# SBH_BMS.net
KiCad netlist of a schematic drawn in Altium Designer
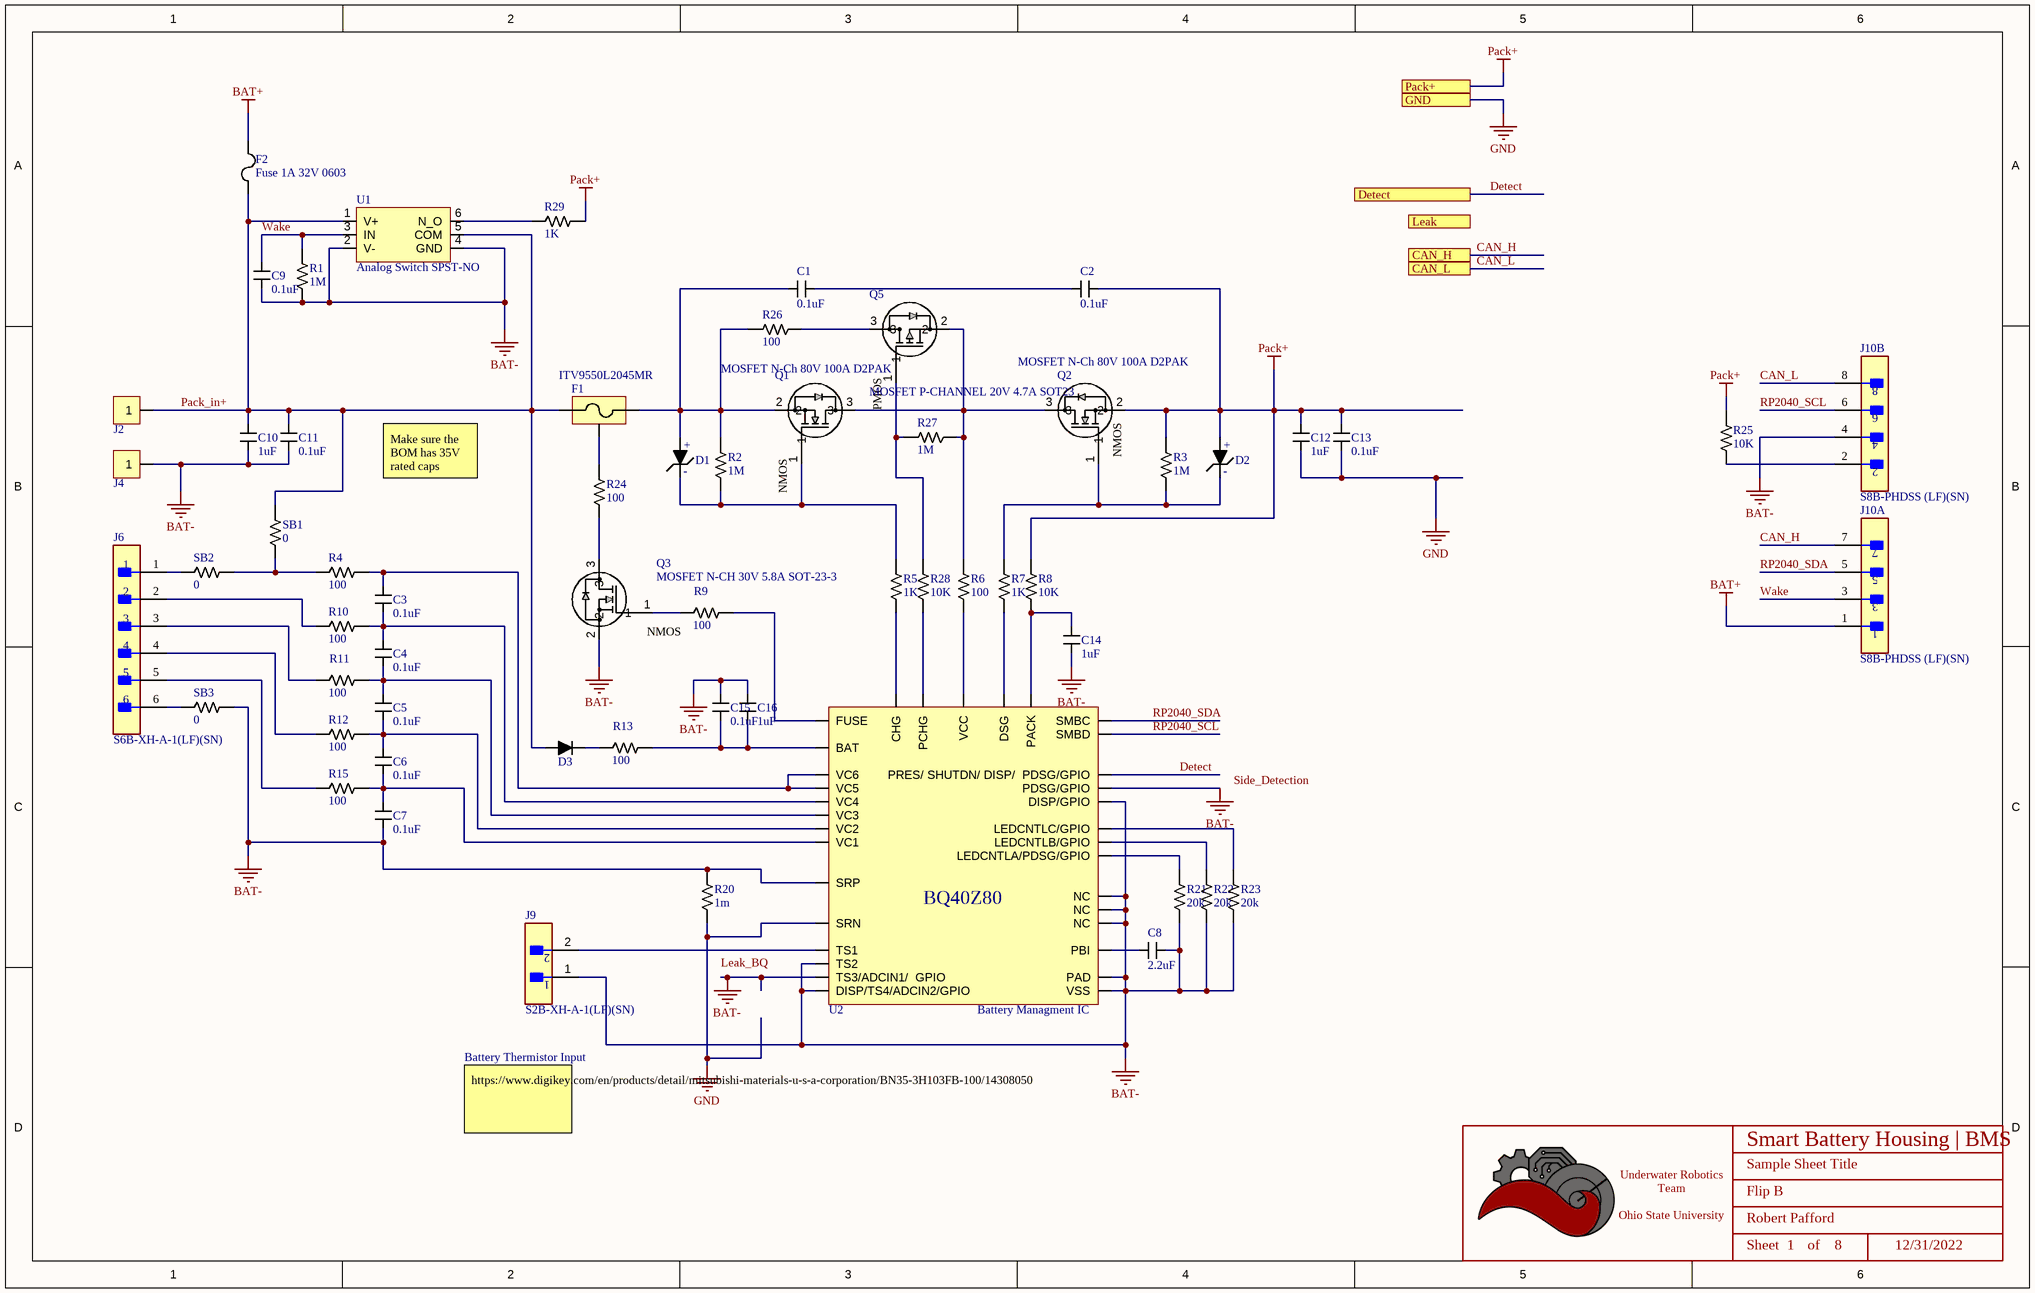
[diagram p0: SBH_BMS.SchDoc]

(export (version "E")
  (design (tool "Eeschema 10.0.6"))
  (components
    (comp (ref "C1")
      (value "0.1uF")
      (footprint "CAPACITOR_0402")
      (description "Cap 100nF 25V +/-10%\r\nCeramic 0402")
      (fields
        (field (name "TOLERANCE") "+/- 10%")
        (field (name "VOLTAGE") "25V")
        (field (name "MADE BY") "Robert Pafford")
      )
      (libsource (lib "Capacitors") (part "CAPACITOR_0.1uF_0402"))
    )
    (comp (ref "C2")
      (value "0.1uF")
      (footprint "CAPACITOR_0402")
      (description "Cap 100nF 25V +/-10%\r\nCeramic 0402")
      (fields
        (field (name "TOLERANCE") "+/- 10%")
        (field (name "VOLTAGE") "25V")
        (field (name "MADE BY") "Robert Pafford")
      )
      (libsource (lib "Capacitors") (part "CAPACITOR_0.1uF_0402"))
    )
    (comp (ref "C3")
      (value "0.1uF")
      (footprint "CAPACITOR_0402")
      (description "Cap 100nF 25V +/-10%\r\nCeramic 0402")
      (fields
        (field (name "TOLERANCE") "+/- 10%")
        (field (name "VOLTAGE") "25V")
        (field (name "MADE BY") "Robert Pafford")
      )
      (libsource (lib "Capacitors") (part "CAPACITOR_0.1uF_0402"))
    )
    (comp (ref "C4")
      (value "0.1uF")
      (footprint "CAPACITOR_0402")
      (description "Cap 100nF 25V +/-10%\r\nCeramic 0402")
      (fields
        (field (name "TOLERANCE") "+/- 10%")
        (field (name "VOLTAGE") "25V")
        (field (name "MADE BY") "Robert Pafford")
      )
      (libsource (lib "Capacitors") (part "CAPACITOR_0.1uF_0402"))
    )
    (comp (ref "C5")
      (value "0.1uF")
      (footprint "CAPACITOR_0402")
      (description "Cap 100nF 25V +/-10%\r\nCeramic 0402")
      (fields
        (field (name "TOLERANCE") "+/- 10%")
        (field (name "VOLTAGE") "25V")
        (field (name "MADE BY") "Robert Pafford")
      )
      (libsource (lib "Capacitors") (part "CAPACITOR_0.1uF_0402"))
    )
    (comp (ref "C6")
      (value "0.1uF")
      (footprint "CAPACITOR_0402")
      (description "Cap 100nF 25V +/-10%\r\nCeramic 0402")
      (fields
        (field (name "TOLERANCE") "+/- 10%")
        (field (name "VOLTAGE") "25V")
        (field (name "MADE BY") "Robert Pafford")
      )
      (libsource (lib "Capacitors") (part "CAPACITOR_0.1uF_0402"))
    )
    (comp (ref "C7")
      (value "0.1uF")
      (footprint "CAPACITOR_0402")
      (description "Cap 100nF 25V +/-10%\r\nCeramic 0402")
      (fields
        (field (name "TOLERANCE") "+/- 10%")
        (field (name "VOLTAGE") "25V")
        (field (name "MADE BY") "Robert Pafford")
      )
      (libsource (lib "Capacitors") (part "CAPACITOR_0.1uF_0402"))
    )
    (comp (ref "C8")
      (value "2.2uF")
      (footprint "CAPACITOR_0402")
      (description "Cap 2.2uF 35V +/-10%\r\nCeramic 0402")
      (fields
        (field (name "TOLERANCE") "+/- 10%")
        (field (name "VOLTAGE") "35V")
        (field (name "MADE BY") "Flip B")
      )
      (libsource (lib "Capacitors") (part "CAPACITOR_2.2uF_0402"))
    )
    (comp (ref "C9")
      (value "0.1uF")
      (footprint "CAPACITOR_0402")
      (description "Cap 100nF 25V +/-10%\r\nCeramic 0402")
      (fields
        (field (name "TOLERANCE") "+/- 10%")
        (field (name "VOLTAGE") "25V")
        (field (name "MADE BY") "Robert Pafford")
      )
      (libsource (lib "Capacitors") (part "CAPACITOR_0.1uF_0402"))
    )
    (comp (ref "C10")
      (value "1uF")
      (footprint "CAPACITOR_0402")
      (description "Cap 1uF 16V +/-10%\r\nCeramic 0402")
      (fields
        (field (name "TOLERANCE") "+/- 10%")
        (field (name "VOLTAGE") "16V")
        (field (name "MADE BY") "Robert Pafford")
      )
      (libsource (lib "Capacitors") (part "CAPACITOR_1uF_0402"))
    )
    (comp (ref "C11")
      (value "0.1uF")
      (footprint "CAPACITOR_0402")
      (description "Cap 100nF 25V +/-10%\r\nCeramic 0402")
      (fields
        (field (name "TOLERANCE") "+/- 10%")
        (field (name "VOLTAGE") "25V")
        (field (name "MADE BY") "Robert Pafford")
      )
      (libsource (lib "Capacitors") (part "CAPACITOR_0.1uF_0402"))
    )
    (comp (ref "C12")
      (value "1uF")
      (footprint "CAPACITOR_0402")
      (description "Cap 1uF 16V +/-10%\r\nCeramic 0402")
      (fields
        (field (name "TOLERANCE") "+/- 10%")
        (field (name "VOLTAGE") "16V")
        (field (name "MADE BY") "Robert Pafford")
      )
      (libsource (lib "Capacitors") (part "CAPACITOR_1uF_0402"))
    )
    (comp (ref "C13")
      (value "0.1uF")
      (footprint "CAPACITOR_0402")
      (description "Cap 100nF 25V +/-10%\r\nCeramic 0402")
      (fields
        (field (name "TOLERANCE") "+/- 10%")
        (field (name "VOLTAGE") "25V")
        (field (name "MADE BY") "Robert Pafford")
      )
      (libsource (lib "Capacitors") (part "CAPACITOR_0.1uF_0402"))
    )
    (comp (ref "C14")
      (value "1uF")
      (footprint "CAPACITOR_0402")
      (description "Cap 1uF 16V +/-10%\r\nCeramic 0402")
      (fields
        (field (name "TOLERANCE") "+/- 10%")
        (field (name "VOLTAGE") "16V")
        (field (name "MADE BY") "Robert Pafford")
      )
      (libsource (lib "Capacitors") (part "CAPACITOR_1uF_0402"))
    )
    (comp (ref "C15")
      (value "0.1uF")
      (footprint "CAPACITOR_0402")
      (description "Cap 100nF 25V +/-10%\r\nCeramic 0402")
      (fields
        (field (name "TOLERANCE") "+/- 10%")
        (field (name "VOLTAGE") "25V")
        (field (name "MADE BY") "Robert Pafford")
      )
      (libsource (lib "Capacitors") (part "CAPACITOR_0.1uF_0402"))
    )
    (comp (ref "C16")
      (value "1uF")
      (footprint "CAPACITOR_0402")
      (description "Cap 1uF 16V +/-10%\r\nCeramic 0402")
      (fields
        (field (name "TOLERANCE") "+/- 10%")
        (field (name "VOLTAGE") "16V")
        (field (name "MADE BY") "Robert Pafford")
      )
      (libsource (lib "Capacitors") (part "CAPACITOR_1uF_0402"))
    )
    (comp (ref "D1")
      (value "Zener_Diode_16V_500mW")
      (footprint "SOD-123")
      (description "Zener Diode ¦ 16 V ¦ 500 mW ¦ SOD-123")
      (fields (field (name "POWER") "500mW") (field (name "MADE BY") "Flip B"))
      (libsource (lib "Diodes") (part "Zener_Diode_16V_500mW"))
    )
    (comp (ref "D2")
      (value "Zener_Diode_16V_500mW")
      (footprint "SOD-123")
      (description "Zener Diode ¦ 16 V ¦ 500 mW ¦ SOD-123")
      (fields (field (name "POWER") "500mW") (field (name "MADE BY") "Flip B"))
      (libsource (lib "Diodes") (part "Zener_Diode_16V_500mW"))
    )
    (comp (ref "D3")
      (value "MBR0520LT3G")
      (footprint "SOD-123")
      (description "Schottky Diode, 20V reverse breakdown, 500mA, Vf = 0.385V")
      (fields (field (name "MADE BY") "Flip B"))
      (libsource (lib "Diodes") (part "SCHOTTKY_20V_500mA"))
    )
    (comp (ref "F1")
      (value "ITV9550L2045MR")
      (footprint "ITV9550")
      (description "LittelFuse  ¦ 45A ¦ 5S ¦ SMD ¦ Self-Control Protector")
      (fields (field (name "CREATED BY") "Flip B"))
      (libsource (lib "Fuses") (part "ITV9550L2045MR"))
    )
    (comp (ref "F2")
      (value "Fuse 1A 32V 0603")
      (footprint "2-SMD Fuse 0603")
      (description "Pansonic ¦ 32V ¦ 1A ¦ 0603 ¦ Fast Blow")
      (fields
        (field (name "MANUFACTURER_PART_NUMBER") "ERB-RE1R00V")
        (field (name "CREATED BY") "Nathan Ayer")
      )
      (libsource (lib "Fuses") (part "ERB-RE1R00V"))
    )
    (comp (ref "J2")
      (value "Redcube M4 Term 85A")
      (footprint "Redcube M4 Term 85A")
      (fields (field (name "CREATED BY") "Nahtan Ayer"))
      (libsource (lib "Connectors") (part "Redcube M4 Term 85A"))
    )
    (comp (ref "J4")
      (value "Redcube M4 Term 85A")
      (footprint "Redcube M4 Term 85A")
      (fields (field (name "CREATED BY") "Nahtan Ayer"))
      (libsource (lib "Connectors") (part "Redcube M4 Term 85A"))
    )
    (comp (ref "J6")
      (value "S6B-XH-A-1(LF)(SN)")
      (footprint "FP-S6B-XH-A-1_LF_SN-MFG")
      (description "CONN HEADER R/A P6OS 2.5MM")
      (libsource (lib "Altium Content Vault") (part "f2cb566baf1c37ab5a3b8e90bbeafd6"))
    )
    (comp (ref "J9")
      (value "S2B-XH-A-1(LF)(SN)")
      (footprint "FP-S2B-XH-A-1_LF_SN-MFG")
      (description "CONN HEADER R/A 2POS 2.5MM")
      (libsource (lib "Altium Content Vault") (part "3bc925449376181038e59eaffc5286c"))
    )
    (comp (ref "J10")
      (value "S8B-PHDSS (LF)(SN)")
      (footprint "FP-S8B-PHDSS_LF_SN-MFG")
      (description "CONN HEADER R/A 8POS 2MM")
      (libsource (lib "Altium Content Vault") (part "811e954b9c034aa737de4d9295cbe7e"))
    )
    (comp (ref "Q1")
      (value "MOSFET N-Ch 80V 100A D2PAK")
      (footprint "D2PAK")
      (description "N-Channel 80V 100A (Ta) 306W (Ta), Surface Mount D2PAK")
      (fields
        (field (name "MANUFACTURER _PART_NUMBER") "PSMN4R4-80BS,118")
        (field (name "CREATED BY") "Flip B")
      )
      (libsource (lib "Transistors") (part "PSMN4R4-80BS,118"))
    )
    (comp (ref "Q2")
      (value "MOSFET N-Ch 80V 100A D2PAK")
      (footprint "D2PAK")
      (description "N-Channel 80V 100A (Ta) 306W (Ta), Surface Mount D2PAK")
      (fields
        (field (name "MANUFACTURER _PART_NUMBER") "PSMN4R4-80BS,118")
        (field (name "CREATED BY") "Flip B")
      )
      (libsource (lib "Transistors") (part "PSMN4R4-80BS,118"))
    )
    (comp (ref "Q3")
      (value "MOSFET N-CH 30V 5.8A SOT-23-3")
      (footprint "SOT-23-3")
      (description "N-Channel 30 V 5.8A (Ta) 1.4W (Ta) Surface Mount SOT-23-3")
      (fields (field (name "MANUFACTURER _PART_NUMBER") "AO3404A") (field (name "CREATED BY") "Dylan T"))
      (libsource (lib "Transistors") (part "AO3404A"))
    )
    (comp (ref "Q5")
      (value "MOSFET P-CHANNEL 20V 4.7A SOT23")
      (footprint "SOT-23-3")
      (description "P-Channel 20 V 4.7A (Tc) 1.56W (Tc) Surface Mount SOT-23")
      (fields
        (field (name "MANUFACTURER_PART_NUMBER") "TSM500P02CX")
        (field (name "CREATED BY") "Robert Pafford")
      )
      (libsource (lib "Transistors") (part "TSM500P02CX"))
    )
    (comp (ref "R1")
      (value "1M")
      (footprint "RESISTOR_0603")
      (description "RES 1M OHM 1/8W 0603")
      (fields
        (field (name "TOLERANCE") "+/- 5%")
        (field (name "VALUE  (OHMS)") "1M")
        (field (name "MADE BY") "Robert Pafford")
      )
      (libsource (lib "Resistors") (part "RESISTOR_1M_0603"))
    )
    (comp (ref "R2")
      (value "1M")
      (footprint "RESISTOR_0603")
      (description "RES 1M OHM 1/8W 0603")
      (fields
        (field (name "TOLERANCE") "+/- 5%")
        (field (name "VALUE  (OHMS)") "1M")
        (field (name "MADE BY") "Robert Pafford")
      )
      (libsource (lib "Resistors") (part "RESISTOR_1M_0603"))
    )
    (comp (ref "R3")
      (value "1M")
      (footprint "RESISTOR_0603")
      (description "RES 1M OHM 1/8W 0603")
      (fields
        (field (name "TOLERANCE") "+/- 5%")
        (field (name "VALUE  (OHMS)") "1M")
        (field (name "MADE BY") "Robert Pafford")
      )
      (libsource (lib "Resistors") (part "RESISTOR_1M_0603"))
    )
    (comp (ref "R4")
      (value "100 Ohm 5% 1/16W")
      (footprint "RESISTOR_0402")
      (description "RES 100 OHM 5% 1/16W 0402")
      (fields
        (field (name "TOLERANCE") "+/- 5%")
        (field (name "VALUE  (OHMS)") "100")
        (field (name "MADE BY") "Flip B")
      )
      (libsource (lib "Resistors") (part "RESISTOR_100_0402"))
    )
    (comp (ref "R5")
      (value "1k Ohm 1% 1/16W")
      (footprint "RESISTOR_0402")
      (description "RES 1k OHM 1% 1/16W 0402")
      (fields
        (field (name "TOLERANCE") "+/- 1%")
        (field (name "VALUE  (OHMS)") "1K")
        (field (name "MADE BY") "Robert Pafford")
      )
      (libsource (lib "Resistors") (part "RESISTOR_1K_0402"))
    )
    (comp (ref "R6")
      (value "100 Ohm 5% 1/16W")
      (footprint "RESISTOR_0402")
      (description "RES 100 OHM 5% 1/16W 0402")
      (fields
        (field (name "TOLERANCE") "+/- 5%")
        (field (name "VALUE  (OHMS)") "100")
        (field (name "MADE BY") "Flip B")
      )
      (libsource (lib "Resistors") (part "RESISTOR_100_0402"))
    )
    (comp (ref "R7")
      (value "1k Ohm 1% 1/16W")
      (footprint "RESISTOR_0402")
      (description "RES 1k OHM 1% 1/16W 0402")
      (fields
        (field (name "TOLERANCE") "+/- 1%")
        (field (name "VALUE  (OHMS)") "1K")
        (field (name "MADE BY") "Robert Pafford")
      )
      (libsource (lib "Resistors") (part "RESISTOR_1K_0402"))
    )
    (comp (ref "R8")
      (value "10k Ohm 1% 1/16W")
      (footprint "RESISTOR_0402")
      (description "RES 10k OHM 1% 1/16W 0402")
      (fields
        (field (name "TOLERANCE") "+/- 1%")
        (field (name "VALUE  (OHMS)") "10K")
        (field (name "MADE BY") "Robert Pafford")
      )
      (libsource (lib "Resistors") (part "RESISTOR_10K_0402"))
    )
    (comp (ref "R9")
      (value "100 Ohm 5% 1/16W")
      (footprint "RESISTOR_0402")
      (description "RES 100 OHM 5% 1/16W 0402")
      (fields
        (field (name "TOLERANCE") "+/- 5%")
        (field (name "VALUE  (OHMS)") "100")
        (field (name "MADE BY") "Flip B")
      )
      (libsource (lib "Resistors") (part "RESISTOR_100_0402"))
    )
    (comp (ref "R10")
      (value "100 Ohm 5% 1/16W")
      (footprint "RESISTOR_0402")
      (description "RES 100 OHM 5% 1/16W 0402")
      (fields
        (field (name "TOLERANCE") "+/- 5%")
        (field (name "VALUE  (OHMS)") "100")
        (field (name "MADE BY") "Flip B")
      )
      (libsource (lib "Resistors") (part "RESISTOR_100_0402"))
    )
    (comp (ref "R11")
      (value "100 Ohm 5% 1/16W")
      (footprint "RESISTOR_0402")
      (description "RES 100 OHM 5% 1/16W 0402")
      (fields
        (field (name "TOLERANCE") "+/- 5%")
        (field (name "VALUE  (OHMS)") "100")
        (field (name "MADE BY") "Flip B")
      )
      (libsource (lib "Resistors") (part "RESISTOR_100_0402"))
    )
    (comp (ref "R12")
      (value "100 Ohm 5% 1/16W")
      (footprint "RESISTOR_0402")
      (description "RES 100 OHM 5% 1/16W 0402")
      (fields
        (field (name "TOLERANCE") "+/- 5%")
        (field (name "VALUE  (OHMS)") "100")
        (field (name "MADE BY") "Flip B")
      )
      (libsource (lib "Resistors") (part "RESISTOR_100_0402"))
    )
    (comp (ref "R13")
      (value "100 Ohm 5% 1/16W")
      (footprint "RESISTOR_0402")
      (description "RES 100 OHM 5% 1/16W 0402")
      (fields
        (field (name "TOLERANCE") "+/- 5%")
        (field (name "VALUE  (OHMS)") "100")
        (field (name "MADE BY") "Flip B")
      )
      (libsource (lib "Resistors") (part "RESISTOR_100_0402"))
    )
    (comp (ref "R15")
      (value "100 Ohm 5% 1/16W")
      (footprint "RESISTOR_0402")
      (description "RES 100 OHM 5% 1/16W 0402")
      (fields
        (field (name "TOLERANCE") "+/- 5%")
        (field (name "VALUE  (OHMS)") "100")
        (field (name "MADE BY") "Flip B")
      )
      (libsource (lib "Resistors") (part "RESISTOR_100_0402"))
    )
    (comp (ref "R20")
      (value "1m Ohm 5% 8W")
      (footprint "RES_CSS2H-3920")
      (description "RES 1m OHM 1% 8W Current Sense")
      (fields
        (field (name "TOLERANCE") "+/- 1%")
        (field (name "VALUE  (OHMS)") "1m")
        (field (name "MADE BY") "Flip B")
      )
      (libsource (lib "Resistors") (part "RESISTOR_1m_CS"))
    )
    (comp (ref "R21")
      (value "20k Ohm 1% 1/16W")
      (footprint "RESISTOR_0402")
      (description "RES 20k OHM 1% 1/16W 0402")
      (fields
        (field (name "TOLERANCE") "+/- 1%")
        (field (name "VALUE  (OHMS)") "20k")
        (field (name "MADE BY") "Flip B")
      )
      (libsource (lib "Resistors") (part "RESISTOR_20K_0402"))
    )
    (comp (ref "R22")
      (value "20k Ohm 1% 1/16W")
      (footprint "RESISTOR_0402")
      (description "RES 20k OHM 1% 1/16W 0402")
      (fields
        (field (name "TOLERANCE") "+/- 1%")
        (field (name "VALUE  (OHMS)") "20k")
        (field (name "MADE BY") "Flip B")
      )
      (libsource (lib "Resistors") (part "RESISTOR_20K_0402"))
    )
    (comp (ref "R23")
      (value "20k Ohm 1% 1/16W")
      (footprint "RESISTOR_0402")
      (description "RES 20k OHM 1% 1/16W 0402")
      (fields
        (field (name "TOLERANCE") "+/- 1%")
        (field (name "VALUE  (OHMS)") "20k")
        (field (name "MADE BY") "Flip B")
      )
      (libsource (lib "Resistors") (part "RESISTOR_20K_0402"))
    )
    (comp (ref "R24")
      (value "100 Ohm 5% 1/16W")
      (footprint "RESISTOR_0402")
      (description "RES 100 OHM 5% 1/16W 0402")
      (fields
        (field (name "TOLERANCE") "+/- 5%")
        (field (name "VALUE  (OHMS)") "100")
        (field (name "MADE BY") "Flip B")
      )
      (libsource (lib "Resistors") (part "RESISTOR_100_0402"))
    )
    (comp (ref "R25")
      (value "10k Ohm 5% 1/10W")
      (footprint "RESISTOR_0603")
      (description "RES 10k OHM 5% 1/10W 0603")
      (fields
        (field (name "TOLERANCE") "+/- 5%")
        (field (name "VALUE  (OHMS)") "10K")
        (field (name "MADE BY") "Robert Pafford")
      )
      (libsource (lib "Resistors") (part "RESISTOR_10K_0603"))
    )
    (comp (ref "R26")
      (value "100 Ohm 5% 1/16W")
      (footprint "RESISTOR_0402")
      (description "RES 100 OHM 5% 1/16W 0402")
      (fields
        (field (name "TOLERANCE") "+/- 5%")
        (field (name "VALUE  (OHMS)") "100")
        (field (name "MADE BY") "Flip B")
      )
      (libsource (lib "Resistors") (part "RESISTOR_100_0402"))
    )
    (comp (ref "R27")
      (value "1M")
      (footprint "RESISTOR_0603")
      (description "RES 1M OHM 1/8W 0603")
      (fields
        (field (name "TOLERANCE") "+/- 5%")
        (field (name "VALUE  (OHMS)") "1M")
        (field (name "MADE BY") "Robert Pafford")
      )
      (libsource (lib "Resistors") (part "RESISTOR_1M_0603"))
    )
    (comp (ref "R28")
      (value "10k Ohm 1% 1/16W")
      (footprint "RESISTOR_0402")
      (description "RES 10k OHM 1% 1/16W 0402")
      (fields
        (field (name "TOLERANCE") "+/- 1%")
        (field (name "VALUE  (OHMS)") "10K")
        (field (name "MADE BY") "Robert Pafford")
      )
      (libsource (lib "Resistors") (part "RESISTOR_10K_0402"))
    )
    (comp (ref "R29")
      (value "1k Ohm 5% 1/8W")
      (footprint "RESISTOR_0603")
      (description "RES 1k OHM 5% 1/8W 0603")
      (fields
        (field (name "TOLERANCE") "+/- 5%")
        (field (name "VALUE  (OHMS)") "1K")
        (field (name "MADE BY") "Robert Pafford")
      )
      (libsource (lib "Resistors") (part "RESISTOR_1K_0603"))
    )
    (comp (ref "SB1")
      (value "0 Ohm Jumper No Fit")
      (footprint "RESISTOR_0603")
      (description "0 Ohm Jumper No Fit for Solder Bridge")
      (fields (field (name "VALUE  (OHMS)") "0") (field (name "MADE BY") "Robert Pafford"))
      (libsource (lib "Resistors") (part "JUMPER_0_0603"))
    )
    (comp (ref "SB2")
      (value "0 Ohm Jumper No Fit")
      (footprint "RESISTOR_0603")
      (description "0 Ohm Jumper No Fit for Solder Bridge")
      (fields (field (name "VALUE  (OHMS)") "0") (field (name "MADE BY") "Robert Pafford"))
      (libsource (lib "Resistors") (part "JUMPER_0_0603"))
    )
    (comp (ref "SB3")
      (value "0 Ohm Jumper No Fit")
      (footprint "RESISTOR_0603")
      (description "0 Ohm Jumper No Fit for Solder Bridge")
      (fields (field (name "VALUE  (OHMS)") "0") (field (name "MADE BY") "Robert Pafford"))
      (libsource (lib "Resistors") (part "JUMPER_0_0603"))
    )
    (comp (ref "U1")
      (value "Analog Switch SPST-NO")
      (footprint "TSOT-23_S6")
      (description "Analog Switch SPST Normally Open")
      (fields
        (field (name "MF") "Analog Devices")
        (field (name "VOLTAGE") "9-36V")
        (field (name "CREATED BY") "Flip B")
      )
      (libsource (lib "Integrated Circuits") (part "MAX4520EUT+T"))
    )
    (comp (ref "U2")
      (value "Battery Managment IC")
      (footprint "VQFN-32")
      (description "Multifuntion Li-ion/ Lipo Battery Pack Managment IC")
      (fields
        (field (name "MANUFACTURER") "Texas Instruments")
        (field (name "PARTNUMBER") "BQ40Z80RSMT")
        (field (name "CREATED BY") "Flip B")
      )
      (libsource (lib "Integrated Circuits") (part "BQ40Z80RSMT"))
    )
  )
  (nets
    (net (code "1") (name "/CAN_H") (class "Default")
      (node (ref "J10") (pin "7") (pinfunction "7_7") (pintype "passive"))
    )
    (net (code "2") (name "/CAN_L") (class "Default")
      (node (ref "J10") (pin "8") (pinfunction "8_8") (pintype "passive"))
    )
    (net (code "3") (name "/Detect") (class "Default")
      (node (ref "U2") (pin "17") (pinfunction "PRES/_SHUTDN/_DISP/__PDSG/GPIO_17") (pintype "passive"))
    )
    (net (code "6") (name "/Pack_in+") (class "Default")
      (node (ref "C10") (pin "1") (pinfunction "1_1") (pintype "passive"))
      (node (ref "C11") (pin "1") (pinfunction "1_1") (pintype "passive"))
      (node (ref "D3") (pin "1") (pinfunction "1_1") (pintype "passive"))
      (node (ref "F1") (pin "2") (pinfunction "2_2") (pintype "passive"))
      (node (ref "F2") (pin "1") (pinfunction "1_1") (pintype "passive"))
      (node (ref "J2") (pin "1") (pinfunction "1_1") (pintype "passive"))
      (node (ref "SB1") (pin "1") (pinfunction "1_1") (pintype "passive"))
      (node (ref "U1") (pin "1") (pinfunction "V+_1") (pintype "passive"))
      (node (ref "U1") (pin "5") (pinfunction "COM_5") (pintype "passive"))
    )
    (net (code "7") (name "/RP2040_SCL") (class "Default")
      (node (ref "J10") (pin "6") (pinfunction "6_6") (pintype "passive"))
      (node (ref "U2") (pin "18") (pinfunction "SMBD_18") (pintype "passive"))
    )
    (net (code "8") (name "/RP2040_SDA") (class "Default")
      (node (ref "J10") (pin "5") (pinfunction "5_5") (pintype "passive"))
      (node (ref "U2") (pin "19") (pinfunction "SMBC_19") (pintype "passive"))
    )
    (net (code "10") (name "/Wake") (class "Default")
      (node (ref "C9") (pin "1") (pinfunction "1_1") (pintype "passive"))
      (node (ref "J10") (pin "3") (pinfunction "3_3") (pintype "passive"))
      (node (ref "R1") (pin "1") (pinfunction "1_1") (pintype "passive"))
      (node (ref "U1") (pin "3") (pinfunction "IN_3") (pintype "passive"))
    )
    (net (code "11") (name "BAT+") (class "Default")
      (node (ref "F2") (pin "2") (pinfunction "2_2") (pintype "passive"))
      (node (ref "J10") (pin "1") (pinfunction "1_1") (pintype "passive"))
    )
    (net (code "12") (name "BAT-") (class "Default")
      (node (ref "C10") (pin "2") (pinfunction "2_2") (pintype "passive"))
      (node (ref "C11") (pin "2") (pinfunction "2_2") (pintype "passive"))
      (node (ref "C14") (pin "2") (pinfunction "2_2") (pintype "passive"))
      (node (ref "C15") (pin "1") (pinfunction "1_1") (pintype "passive"))
      (node (ref "C16") (pin "1") (pinfunction "1_1") (pintype "passive"))
      (node (ref "C7") (pin "2") (pinfunction "2_2") (pintype "passive"))
      (node (ref "C8") (pin "1") (pinfunction "1_1") (pintype "passive"))
      (node (ref "C9") (pin "2") (pinfunction "2_2") (pintype "passive"))
      (node (ref "J10") (pin "4") (pinfunction "4_4") (pintype "passive"))
      (node (ref "J4") (pin "1") (pinfunction "1_1") (pintype "passive"))
      (node (ref "J9") (pin "1") (pinfunction "1_1") (pintype "passive"))
      (node (ref "Q3") (pin "2") (pinfunction "2_2") (pintype "passive"))
      (node (ref "R1") (pin "2") (pinfunction "2_2") (pintype "passive"))
      (node (ref "R20") (pin "1") (pinfunction "1_1") (pintype "passive"))
      (node (ref "R21") (pin "2") (pinfunction "2_2") (pintype "passive"))
      (node (ref "R22") (pin "2") (pinfunction "2_2") (pintype "passive"))
      (node (ref "R23") (pin "2") (pinfunction "2_2") (pintype "passive"))
      (node (ref "SB3") (pin "1") (pinfunction "1_1") (pintype "passive"))
      (node (ref "U1") (pin "2") (pinfunction "V-_2") (pintype "power_in"))
      (node (ref "U1") (pin "4") (pinfunction "GND_4") (pintype "passive"))
      (node (ref "U2") (pin "11") (pinfunction "TS2_11") (pintype "passive"))
      (node (ref "U2") (pin "12") (pinfunction "TS3/ADCIN1/__GPIO_12") (pintype "passive"))
      (node (ref "U2") (pin "13") (pinfunction "DISP/TS4/ADCIN2/GPIO_13") (pintype "passive"))
      (node (ref "U2") (pin "14") (pinfunction "NC_14") (pintype "passive"))
      (node (ref "U2") (pin "15") (pinfunction "DISP/GPIO_15") (pintype "passive"))
      (node (ref "U2") (pin "16") (pinfunction "PDSG/GPIO_16") (pintype "passive"))
      (node (ref "U2") (pin "27") (pinfunction "NC_27") (pintype "passive"))
      (node (ref "U2") (pin "33") (pinfunction "PAD_33") (pintype "passive"))
      (node (ref "U2") (pin "7") (pinfunction "NC_7") (pintype "passive"))
      (node (ref "U2") (pin "8") (pinfunction "SRP_8") (pintype "passive"))
      (node (ref "U2") (pin "9") (pinfunction "VSS_9") (pintype "passive"))
    )
    (net (code "13") (name "GND") (class "Default")
      (node (ref "C12") (pin "2") (pinfunction "2_2") (pintype "passive"))
      (node (ref "C13") (pin "2") (pinfunction "2_2") (pintype "passive"))
      (node (ref "R20") (pin "2") (pinfunction "2_2") (pintype "passive"))
      (node (ref "U2") (pin "6") (pinfunction "SRN_6") (pintype "passive"))
    )
    (net (code "14") (name "Net-(C1-Pad1)") (class "Default")
      (node (ref "C1") (pin "1") (pinfunction "1_1") (pintype "passive"))
      (node (ref "C2") (pin "2") (pinfunction "2_2") (pintype "passive"))
    )
    (net (code "15") (name "Net-(C1-Pad2)") (class "Default")
      (node (ref "C1") (pin "2") (pinfunction "2_2") (pintype "passive"))
      (node (ref "D1") (pin "1") (pinfunction "1_1") (pintype "passive"))
      (node (ref "F1") (pin "1") (pinfunction "1_1") (pintype "passive"))
      (node (ref "Q1") (pin "2") (pinfunction "2_2") (pintype "passive"))
      (node (ref "R2") (pin "1") (pinfunction "1_1") (pintype "passive"))
      (node (ref "R26") (pin "1") (pinfunction "1_1") (pintype "passive"))
    )
    (net (code "16") (name "Net-(D1-Pad2)") (class "Default")
      (node (ref "D1") (pin "2") (pinfunction "2_2") (pintype "passive"))
      (node (ref "Q1") (pin "1") (pinfunction "1_1") (pintype "passive"))
      (node (ref "R2") (pin "2") (pinfunction "2_2") (pintype "passive"))
      (node (ref "R5") (pin "1") (pinfunction "1_1") (pintype "passive"))
    )
    (net (code "17") (name "Net-(D2-Pad2)") (class "Default")
      (node (ref "D2") (pin "2") (pinfunction "2_2") (pintype "passive"))
      (node (ref "Q2") (pin "1") (pinfunction "1_1") (pintype "passive"))
      (node (ref "R3") (pin "2") (pinfunction "2_2") (pintype "passive"))
      (node (ref "R7") (pin "1") (pinfunction "1_1") (pintype "passive"))
    )
    (net (code "18") (name "Net-(D3-Pad2)") (class "Default")
      (node (ref "D3") (pin "2") (pinfunction "2_2") (pintype "passive"))
      (node (ref "R13") (pin "2") (pinfunction "2_2") (pintype "passive"))
    )
    (net (code "19") (name "Net-(F1-Pad3)") (class "Default")
      (node (ref "F1") (pin "3") (pinfunction "3_3") (pintype "passive"))
      (node (ref "R24") (pin "1") (pinfunction "1_1") (pintype "passive"))
    )
    (net (code "20") (name "Net-(J6-Pad1)") (class "Default")
      (node (ref "J6") (pin "1") (pinfunction "1_1") (pintype "passive"))
      (node (ref "SB2") (pin "2") (pinfunction "2_2") (pintype "passive"))
    )
    (net (code "21") (name "Net-(J6-Pad2)") (class "Default")
      (node (ref "J6") (pin "2") (pinfunction "2_2") (pintype "passive"))
      (node (ref "R10") (pin "2") (pinfunction "2_2") (pintype "passive"))
    )
    (net (code "22") (name "Net-(J6-Pad3)") (class "Default")
      (node (ref "J6") (pin "3") (pinfunction "3_3") (pintype "passive"))
      (node (ref "R11") (pin "2") (pinfunction "2_2") (pintype "passive"))
    )
    (net (code "23") (name "Net-(J6-Pad4)") (class "Default")
      (node (ref "J6") (pin "4") (pinfunction "4_4") (pintype "passive"))
      (node (ref "R12") (pin "2") (pinfunction "2_2") (pintype "passive"))
    )
    (net (code "24") (name "Net-(J6-Pad5)") (class "Default")
      (node (ref "J6") (pin "5") (pinfunction "5_5") (pintype "passive"))
      (node (ref "R15") (pin "2") (pinfunction "2_2") (pintype "passive"))
    )
    (net (code "25") (name "Net-(J6-Pad6)") (class "Default")
      (node (ref "J6") (pin "6") (pinfunction "6_6") (pintype "passive"))
      (node (ref "SB3") (pin "2") (pinfunction "2_2") (pintype "passive"))
    )
    (net (code "26") (name "Net-(J10-Pad2)") (class "Default")
      (node (ref "J10") (pin "2") (pinfunction "2_2") (pintype "passive"))
      (node (ref "R25") (pin "2") (pinfunction "2_2") (pintype "passive"))
    )
    (net (code "27") (name "Net-(Q1-Pad3)") (class "Default")
      (node (ref "Q1") (pin "3") (pinfunction "3_3") (pintype "passive"))
      (node (ref "Q2") (pin "3") (pinfunction "3_3") (pintype "passive"))
      (node (ref "Q5") (pin "2") (pinfunction "2_2") (pintype "passive"))
      (node (ref "R27") (pin "2") (pinfunction "2_2") (pintype "passive"))
      (node (ref "R6") (pin "1") (pinfunction "1_1") (pintype "passive"))
    )
    (net (code "28") (name "Net-(Q3-Pad1)") (class "Default")
      (node (ref "Q3") (pin "1") (pinfunction "1_1") (pintype "passive"))
      (node (ref "R9") (pin "2") (pinfunction "2_2") (pintype "passive"))
    )
    (net (code "29") (name "Net-(Q3-Pad3)") (class "Default")
      (node (ref "Q3") (pin "3") (pinfunction "3_3") (pintype "passive"))
      (node (ref "R24") (pin "2") (pinfunction "2_2") (pintype "passive"))
    )
    (net (code "30") (name "Net-(Q5-Pad1)") (class "Default")
      (node (ref "Q5") (pin "1") (pinfunction "1_1") (pintype "passive"))
      (node (ref "R27") (pin "1") (pinfunction "1_1") (pintype "passive"))
      (node (ref "R28") (pin "1") (pinfunction "1_1") (pintype "passive"))
    )
    (net (code "31") (name "Net-(Q5-Pad3)") (class "Default")
      (node (ref "Q5") (pin "3") (pinfunction "3_3") (pintype "passive"))
      (node (ref "R26") (pin "2") (pinfunction "2_2") (pintype "passive"))
    )
    (net (code "32") (name "Net-(R4-Pad2)") (class "Default")
      (node (ref "R4") (pin "2") (pinfunction "2_2") (pintype "passive"))
      (node (ref "SB1") (pin "2") (pinfunction "2_2") (pintype "passive"))
      (node (ref "SB2") (pin "1") (pinfunction "1_1") (pintype "passive"))
    )
    (net (code "33") (name "Net-(U1-N_O)") (class "Default")
      (node (ref "R29") (pin "2") (pinfunction "2_2") (pintype "passive"))
      (node (ref "U1") (pin "6") (pinfunction "N_O_6") (pintype "passive"))
    )
    (net (code "34") (name "Net-(U2-BAT)") (class "Default")
      (node (ref "C15") (pin "2") (pinfunction "2_2") (pintype "passive"))
      (node (ref "C16") (pin "2") (pinfunction "2_2") (pintype "passive"))
      (node (ref "R13") (pin "1") (pinfunction "1_1") (pintype "passive"))
      (node (ref "U2") (pin "30") (pinfunction "BAT_30") (pintype "passive"))
    )
    (net (code "35") (name "Net-(U2-CHG)") (class "Default")
      (node (ref "R5") (pin "2") (pinfunction "2_2") (pintype "passive"))
      (node (ref "U2") (pin "29") (pinfunction "CHG_29") (pintype "passive"))
    )
    (net (code "36") (name "Net-(U2-DSG)") (class "Default")
      (node (ref "R7") (pin "2") (pinfunction "2_2") (pintype "passive"))
      (node (ref "U2") (pin "26") (pinfunction "DSG_26") (pintype "passive"))
    )
    (net (code "37") (name "Net-(U2-FUSE)") (class "Default")
      (node (ref "R9") (pin "1") (pinfunction "1_1") (pintype "passive"))
      (node (ref "U2") (pin "23") (pinfunction "FUSE_23") (pintype "passive"))
    )
    (net (code "38") (name "Net-(U2-LEDCNTLA{slash}PDSG{slash}GPIO)") (class "Default")
      (node (ref "R21") (pin "1") (pinfunction "1_1") (pintype "passive"))
      (node (ref "U2") (pin "20") (pinfunction "LEDCNTLA/PDSG/GPIO_20") (pintype "passive"))
    )
    (net (code "39") (name "Net-(U2-LEDCNTLB{slash}GPIO)") (class "Default")
      (node (ref "R22") (pin "1") (pinfunction "1_1") (pintype "passive"))
      (node (ref "U2") (pin "21") (pinfunction "LEDCNTLB/GPIO_21") (pintype "passive"))
    )
    (net (code "40") (name "Net-(U2-LEDCNTLC{slash}GPIO)") (class "Default")
      (node (ref "R23") (pin "1") (pinfunction "1_1") (pintype "passive"))
      (node (ref "U2") (pin "22") (pinfunction "LEDCNTLC/GPIO_22") (pintype "passive"))
    )
    (net (code "41") (name "Net-(U2-PACK)") (class "Default")
      (node (ref "C14") (pin "1") (pinfunction "1_1") (pintype "passive"))
      (node (ref "R8") (pin "2") (pinfunction "2_2") (pintype "passive"))
      (node (ref "U2") (pin "25") (pinfunction "PACK_25") (pintype "passive"))
    )
    (net (code "42") (name "Net-(U2-PBI)") (class "Default")
      (node (ref "C8") (pin "2") (pinfunction "2_2") (pintype "passive"))
      (node (ref "U2") (pin "31") (pinfunction "PBI_31") (pintype "passive"))
    )
    (net (code "43") (name "Net-(U2-PCHG)") (class "Default")
      (node (ref "R28") (pin "2") (pinfunction "2_2") (pintype "passive"))
      (node (ref "U2") (pin "28") (pinfunction "PCHG_28") (pintype "passive"))
    )
    (net (code "44") (name "Net-(U2-TS1)") (class "Default")
      (node (ref "J9") (pin "2") (pinfunction "2_2") (pintype "passive"))
      (node (ref "U2") (pin "10") (pinfunction "TS1_10") (pintype "passive"))
    )
    (net (code "45") (name "Net-(U2-VC1)") (class "Default")
      (node (ref "C6") (pin "2") (pinfunction "2_2") (pintype "passive"))
      (node (ref "C7") (pin "1") (pinfunction "1_1") (pintype "passive"))
      (node (ref "R15") (pin "1") (pinfunction "1_1") (pintype "passive"))
      (node (ref "U2") (pin "5") (pinfunction "VC1_5") (pintype "passive"))
    )
    (net (code "46") (name "Net-(U2-VC2)") (class "Default")
      (node (ref "C5") (pin "2") (pinfunction "2_2") (pintype "passive"))
      (node (ref "C6") (pin "1") (pinfunction "1_1") (pintype "passive"))
      (node (ref "R12") (pin "1") (pinfunction "1_1") (pintype "passive"))
      (node (ref "U2") (pin "4") (pinfunction "VC2_4") (pintype "passive"))
    )
    (net (code "47") (name "Net-(U2-VC3)") (class "Default")
      (node (ref "C4") (pin "2") (pinfunction "2_2") (pintype "passive"))
      (node (ref "C5") (pin "1") (pinfunction "1_1") (pintype "passive"))
      (node (ref "R11") (pin "1") (pinfunction "1_1") (pintype "passive"))
      (node (ref "U2") (pin "3") (pinfunction "VC3_3") (pintype "passive"))
    )
    (net (code "48") (name "Net-(U2-VC4)") (class "Default")
      (node (ref "C3") (pin "2") (pinfunction "2_2") (pintype "passive"))
      (node (ref "C4") (pin "1") (pinfunction "1_1") (pintype "passive"))
      (node (ref "R10") (pin "1") (pinfunction "1_1") (pintype "passive"))
      (node (ref "U2") (pin "2") (pinfunction "VC4_2") (pintype "passive"))
    )
    (net (code "49") (name "Net-(U2-VC5)") (class "Default")
      (node (ref "C3") (pin "1") (pinfunction "1_1") (pintype "passive"))
      (node (ref "R4") (pin "1") (pinfunction "1_1") (pintype "passive"))
      (node (ref "U2") (pin "1") (pinfunction "VC5_1") (pintype "passive"))
      (node (ref "U2") (pin "32") (pinfunction "VC6_32") (pintype "passive"))
    )
    (net (code "50") (name "Net-(U2-VCC)") (class "Default")
      (node (ref "R6") (pin "2") (pinfunction "2_2") (pintype "passive"))
      (node (ref "U2") (pin "24") (pinfunction "VCC_24") (pintype "passive"))
    )
    (net (code "51") (name "Pack+") (class "Default")
      (node (ref "C12") (pin "1") (pinfunction "1_1") (pintype "passive"))
      (node (ref "C13") (pin "1") (pinfunction "1_1") (pintype "passive"))
      (node (ref "C2") (pin "1") (pinfunction "1_1") (pintype "passive"))
      (node (ref "D2") (pin "1") (pinfunction "1_1") (pintype "passive"))
      (node (ref "Q2") (pin "2") (pinfunction "2_2") (pintype "passive"))
      (node (ref "R25") (pin "1") (pinfunction "1_1") (pintype "passive"))
      (node (ref "R29") (pin "1") (pinfunction "1_1") (pintype "passive"))
      (node (ref "R3") (pin "1") (pinfunction "1_1") (pintype "passive"))
      (node (ref "R8") (pin "1") (pinfunction "1_1") (pintype "passive"))
    )
  )
)
